# VVblock.net
KiCad netlist of a schematic drawn in Altium Designer
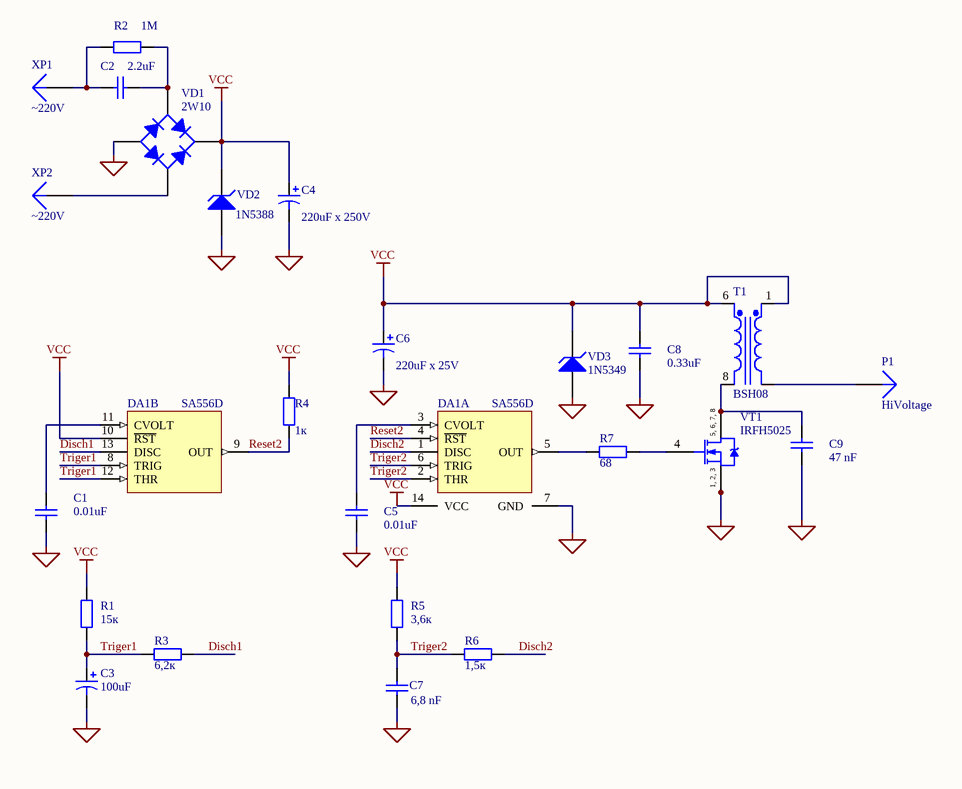
[diagram p0: VVblock.SchDoc]

(export (version "E")
  (design (tool "Eeschema 10.0.6"))
  (components
    (comp (ref "C1")
      (value "0.01uF")
      (footprint "CAPC2012N")
      (description "Capacitor")
      (fields (field (name "Comment") "Cap") (field (name "PUBLISHER") "Altium Limited"))
      (libsource (lib "Miscellaneous Devices") (part "Cap"))
    )
    (comp (ref "C2")
      (value "2.2uF")
      (footprint "RAD-0.3")
      (description "Capacitor")
      (fields (field (name "Comment") "Cap") (field (name "PUBLISHER") "Altium Limited"))
      (libsource (lib "Miscellaneous Devices") (part "Cap"))
    )
    (comp (ref "C3")
      (value "100uF")
      (footprint "CAPPR2.5-6.3x11")
      (description "Polarized Capacitor (Radial)")
      (fields (field (name "Comment") "Cap Pol1") (field (name "PUBLISHER") "Altium Limited"))
      (libsource (lib "Miscellaneous Devices") (part "Cap Pol1"))
    )
    (comp (ref "C4")
      (value "220uF x 250V")
      (footprint "CAPPR5-10x20")
      (description "Polarized Capacitor (Radial)")
      (fields (field (name "Comment") "Cap Pol1") (field (name "PUBLISHER") "Altium Limited"))
      (libsource (lib "Miscellaneous Devices") (part "Cap Pol1"))
    )
    (comp (ref "C5")
      (value "0.01uF")
      (footprint "CAPC2012N")
      (description "Capacitor")
      (fields (field (name "Comment") "Cap") (field (name "PUBLISHER") "Altium Limited"))
      (libsource (lib "Miscellaneous Devices") (part "Cap"))
    )
    (comp (ref "C6")
      (value "220uF x 25V")
      (footprint "CAPPR5-10x20")
      (description "Polarized Capacitor (Radial)")
      (fields (field (name "Comment") "Cap Pol1") (field (name "PUBLISHER") "Altium Limited"))
      (libsource (lib "Miscellaneous Devices") (part "Cap Pol1"))
    )
    (comp (ref "C7")
      (value "6,8 nF")
      (footprint "CAPC2012N")
      (description "Capacitor")
      (fields (field (name "Comment") "Cap") (field (name "PUBLISHER") "Altium Limited"))
      (libsource (lib "Miscellaneous Devices") (part "Cap"))
    )
    (comp (ref "C8")
      (value "0.33uF")
      (footprint "CAPC2012N")
      (description "Capacitor")
      (fields (field (name "Comment") "Cap") (field (name "PUBLISHER") "Altium Limited"))
      (libsource (lib "Miscellaneous Devices") (part "Cap"))
    )
    (comp (ref "C9")
      (value "47 nF")
      (footprint "CAPC2012N")
      (description "Capacitor")
      (fields (field (name "Comment") "Cap") (field (name "PUBLISHER") "Altium Limited"))
      (libsource (lib "Miscellaneous Devices") (part "Cap"))
    )
    (comp (ref "DA1")
      (value "SA556D")
      (footprint "SO14_N")
      (description "General-Purpose Dual Bipolar Timer")
      (fields (field (name "PUBLISHER") "Altium Limited"))
      (libsource (lib "ST Analog Timer Circuit") (part "SA556D"))
    )
    (comp (ref "P1")
      (value "HiVoltage")
      (footprint "PIN1")
      (description "Plug")
      (fields (field (name "PUBLISHER") "Altium Limited"))
      (libsource (lib "Miscellaneous Connectors") (part "Plug"))
    )
    (comp (ref "R1")
      (value "15к")
      (footprint "resc2012N")
      (description "Resistor")
      (fields (field (name "Comment") "Res2") (field (name "PUBLISHER") "Altium Limited"))
      (libsource (lib "Miscellaneous Devices") (part "Res2"))
    )
    (comp (ref "R2")
      (value "1M")
      (footprint "AXIAL-0.4")
      (description "Resistor")
      (fields (field (name "Comment") "Res2") (field (name "PUBLISHER") "Altium Limited"))
      (libsource (lib "") (part "Res2_2"))
    )
    (comp (ref "R3")
      (value "6,2к")
      (footprint "RESC2012N")
      (description "Resistor")
      (fields (field (name "Comment") "Res2") (field (name "PUBLISHER") "Altium Limited"))
      (libsource (lib "") (part "Res2_1"))
    )
    (comp (ref "R4")
      (value "1к")
      (footprint "RESC2012N")
      (description "Resistor")
      (fields (field (name "Comment") "Res2") (field (name "PUBLISHER") "Altium Limited"))
      (libsource (lib "Miscellaneous Devices") (part "Res2"))
    )
    (comp (ref "R5")
      (value "3,6к")
      (footprint "RESC2012N")
      (description "Resistor")
      (fields (field (name "Comment") "Res2") (field (name "PUBLISHER") "Altium Limited"))
      (libsource (lib "Miscellaneous Devices") (part "Res2"))
    )
    (comp (ref "R6")
      (value "1,5к")
      (footprint "RESC2012N")
      (description "Resistor")
      (fields (field (name "Comment") "Res2") (field (name "PUBLISHER") "Altium Limited"))
      (libsource (lib "") (part "Res2_1"))
    )
    (comp (ref "R7")
      (value "68")
      (footprint "RESC2012N")
      (description "Resistor")
      (fields (field (name "Comment") "Res2") (field (name "PUBLISHER") "Altium Limited"))
      (libsource (lib "") (part "Res2_1"))
    )
    (comp (ref "T1")
      (value "BSH08")
      (footprint "TRF_4")
      (description "Transformer (Coupled Inductor Model)")
      (fields (field (name "PUBLISHER") "Altium Limited"))
      (libsource (lib "VVBlock") (part "Trans Cupl"))
    )
    (comp (ref "VD1")
      (value "2W10")
      (footprint "SW/PB-V4/H7.1")
      (description "Full Wave Diode Bridge")
      (fields (field (name "PUBLISHER") "Altium Limited"))
      (libsource (lib "Miscellaneous Devices") (part "Bridge1"))
    )
    (comp (ref "VD2")
      (value "1N5388")
      (footprint "DIODE-0.7")
      (description "Zener Diode")
      (fields (field (name "PUBLISHER") "Altium Limited"))
      (libsource (lib "Miscellaneous Devices") (part "D Zener"))
    )
    (comp (ref "VD3")
      (value "1N5349")
      (footprint "DIODE-0.7")
      (description "Zener Diode")
      (fields (field (name "PUBLISHER") "Altium Limited"))
      (libsource (lib "Miscellaneous Devices") (part "D Zener"))
    )
    (comp (ref "VT1")
      (value "IRFH5025")
      (footprint "SO-8_N")
      (description "HEXFET Power MOSFET")
      (fields (field (name "PUBLISHER") "Altium Limited"))
      (libsource (lib "IR Discrete MOSFET - Power") (part "IRF7474"))
    )
    (comp (ref "XP1")
      (value "~220V")
      (footprint "PIN1")
      (description "Plug")
      (fields (field (name "PUBLISHER") "Altium Limited"))
      (libsource (lib "Miscellaneous Connectors") (part "Plug"))
    )
    (comp (ref "XP2")
      (value "~220V")
      (footprint "PIN1")
      (description "Plug")
      (fields (field (name "PUBLISHER") "Altium Limited"))
      (libsource (lib "Miscellaneous Connectors") (part "Plug"))
    )
  )
  (nets
    (net (code "1") (name "/Disch1") (class "Default")
      (node (ref "DA1") (pin "13") (pinfunction "DISC_13") (pintype "open_collector"))
      (node (ref "R3") (pin "1") (pinfunction "1_1") (pintype "passive"))
    )
    (net (code "2") (name "/Disch2") (class "Default")
      (node (ref "DA1") (pin "1") (pinfunction "DISC_1") (pintype "open_collector"))
      (node (ref "R6") (pin "1") (pinfunction "1_1") (pintype "passive"))
    )
    (net (code "3") (name "/Reset2") (class "Default")
      (node (ref "DA1") (pin "4") (pinfunction "~{RST}_4") (pintype "input"))
      (node (ref "DA1") (pin "9") (pinfunction "OUT_9") (pintype "output"))
      (node (ref "R4") (pin "1") (pinfunction "1_1") (pintype "passive"))
    )
    (net (code "4") (name "/Triger1") (class "Default")
      (node (ref "C3") (pin "1") (pinfunction "1_1") (pintype "passive"))
      (node (ref "DA1") (pin "12") (pinfunction "THR_12") (pintype "input"))
      (node (ref "DA1") (pin "8") (pinfunction "TRIG_8") (pintype "input"))
      (node (ref "R1") (pin "1") (pinfunction "1_1") (pintype "passive"))
      (node (ref "R3") (pin "2") (pinfunction "2_2") (pintype "passive"))
    )
    (net (code "5") (name "/Triger2") (class "Default")
      (node (ref "C7") (pin "2") (pinfunction "2_2") (pintype "passive"))
      (node (ref "DA1") (pin "2") (pinfunction "THR_2") (pintype "input"))
      (node (ref "DA1") (pin "6") (pinfunction "TRIG_6") (pintype "input"))
      (node (ref "R5") (pin "1") (pinfunction "1_1") (pintype "passive"))
      (node (ref "R6") (pin "2") (pinfunction "2_2") (pintype "passive"))
    )
    (net (code "6") (name "GND") (class "Default")
      (node (ref "C1") (pin "1") (pinfunction "1_1") (pintype "passive"))
      (node (ref "C3") (pin "2") (pinfunction "2_2") (pintype "passive"))
      (node (ref "C4") (pin "2") (pinfunction "2_2") (pintype "passive"))
      (node (ref "C5") (pin "1") (pinfunction "1_1") (pintype "passive"))
      (node (ref "C6") (pin "2") (pinfunction "2_2") (pintype "passive"))
      (node (ref "C7") (pin "1") (pinfunction "1_1") (pintype "passive"))
      (node (ref "C8") (pin "1") (pinfunction "1_1") (pintype "passive"))
      (node (ref "C9") (pin "1") (pinfunction "1_1") (pintype "passive"))
      (node (ref "DA1") (pin "7") (pinfunction "GND_7") (pintype "power_in"))
      (node (ref "VD1") (pin "3") (pinfunction "A_3") (pintype "passive"))
      (node (ref "VD2") (pin "1") (pinfunction "A_1") (pintype "passive"))
      (node (ref "VD3") (pin "1") (pinfunction "A_1") (pintype "passive"))
      (node (ref "VT1") (pin "1") (pinfunction "S_1") (pintype "passive"))
      (node (ref "VT1") (pin "2") (pinfunction "S_2") (pintype "passive"))
      (node (ref "VT1") (pin "3") (pinfunction "S_3") (pintype "passive"))
    )
    (net (code "7") (name "Net-(C2-Pad1)") (class "Default")
      (node (ref "C2") (pin "1") (pinfunction "1_1") (pintype "passive"))
      (node (ref "R2") (pin "2") (pinfunction "2_2") (pintype "passive"))
      (node (ref "VD1") (pin "4") (pinfunction "C_4") (pintype "passive"))
    )
    (net (code "8") (name "Net-(C2-Pad2)") (class "Default")
      (node (ref "C2") (pin "2") (pinfunction "2_2") (pintype "passive"))
      (node (ref "R2") (pin "1") (pinfunction "1_1") (pintype "passive"))
      (node (ref "XP1") (pin "1") (pinfunction "1_1") (pintype "passive"))
    )
    (net (code "9") (name "Net-(DA1A-CVOLT)") (class "Default")
      (node (ref "C5") (pin "2") (pinfunction "2_2") (pintype "passive"))
      (node (ref "DA1") (pin "3") (pinfunction "CVOLT_3") (pintype "input"))
    )
    (net (code "10") (name "Net-(DA1A-OUT)") (class "Default")
      (node (ref "DA1") (pin "5") (pinfunction "OUT_5") (pintype "output"))
      (node (ref "R7") (pin "2") (pinfunction "2_2") (pintype "passive"))
    )
    (net (code "11") (name "Net-(DA1B-CVOLT)") (class "Default")
      (node (ref "C1") (pin "2") (pinfunction "2_2") (pintype "passive"))
      (node (ref "DA1") (pin "11") (pinfunction "CVOLT_11") (pintype "input"))
    )
    (net (code "12") (name "Net-(T1-Anode_CRT)") (class "Default")
      (node (ref "P1") (pin "1") (pinfunction "1_1") (pintype "passive"))
      (node (ref "T1") (pin "4") (pinfunction "Anode_CRT_4") (pintype "passive"))
    )
    (net (code "13") (name "Net-(T1-Collector)") (class "Default")
      (node (ref "C9") (pin "2") (pinfunction "2_2") (pintype "passive"))
      (node (ref "T1") (pin "8") (pinfunction "Collector_8") (pintype "passive"))
      (node (ref "VT1") (pin "5") (pinfunction "D_5") (pintype "passive"))
      (node (ref "VT1") (pin "6") (pinfunction "D_6") (pintype "passive"))
      (node (ref "VT1") (pin "7") (pinfunction "D_7") (pintype "passive"))
      (node (ref "VT1") (pin "8") (pinfunction "D_8") (pintype "passive"))
    )
    (net (code "14") (name "Net-(VD1-C-Pad2)") (class "Default")
      (node (ref "VD1") (pin "2") (pinfunction "C_2") (pintype "passive"))
      (node (ref "XP2") (pin "1") (pinfunction "1_1") (pintype "passive"))
    )
    (net (code "15") (name "Net-(VT1-G)") (class "Default")
      (node (ref "R7") (pin "1") (pinfunction "1_1") (pintype "passive"))
      (node (ref "VT1") (pin "4") (pinfunction "G_4") (pintype "passive"))
    )
    (net (code "16") (name "VCC") (class "Default")
      (node (ref "C4") (pin "1") (pinfunction "1_1") (pintype "passive"))
      (node (ref "C6") (pin "1") (pinfunction "1_1") (pintype "passive"))
      (node (ref "C8") (pin "2") (pinfunction "2_2") (pintype "passive"))
      (node (ref "DA1") (pin "10") (pinfunction "~{RST}_10") (pintype "passive"))
      (node (ref "DA1") (pin "14") (pinfunction "VCC_14") (pintype "power_in"))
      (node (ref "R1") (pin "2") (pinfunction "2_2") (pintype "passive"))
      (node (ref "R4") (pin "2") (pinfunction "2_2") (pintype "passive"))
      (node (ref "R5") (pin "2") (pinfunction "2_2") (pintype "passive"))
      (node (ref "T1") (pin "1") (pinfunction "ABL_1") (pintype "passive"))
      (node (ref "T1") (pin "6") (pinfunction "+B_6") (pintype "passive"))
      (node (ref "VD1") (pin "1") (pinfunction "K_1") (pintype "passive"))
      (node (ref "VD2") (pin "2") (pinfunction "K_2") (pintype "passive"))
      (node (ref "VD3") (pin "2") (pinfunction "K_2") (pintype "passive"))
    )
    (net (code "17") (name "unconnected-(DA1B-GND-Pad7)") (class "Default")
      (node (ref "DA1") (pin "7") (pinfunction "GND_7") (pintype "power_in"))
    )
    (net (code "18") (name "unconnected-(DA1B-VCC-Pad14)") (class "Default")
      (node (ref "DA1") (pin "14") (pinfunction "VCC_14") (pintype "power_in"))
    )
  )
)
